# schematic.net
KiCad netlist of a schematic drawn in EasyEDA
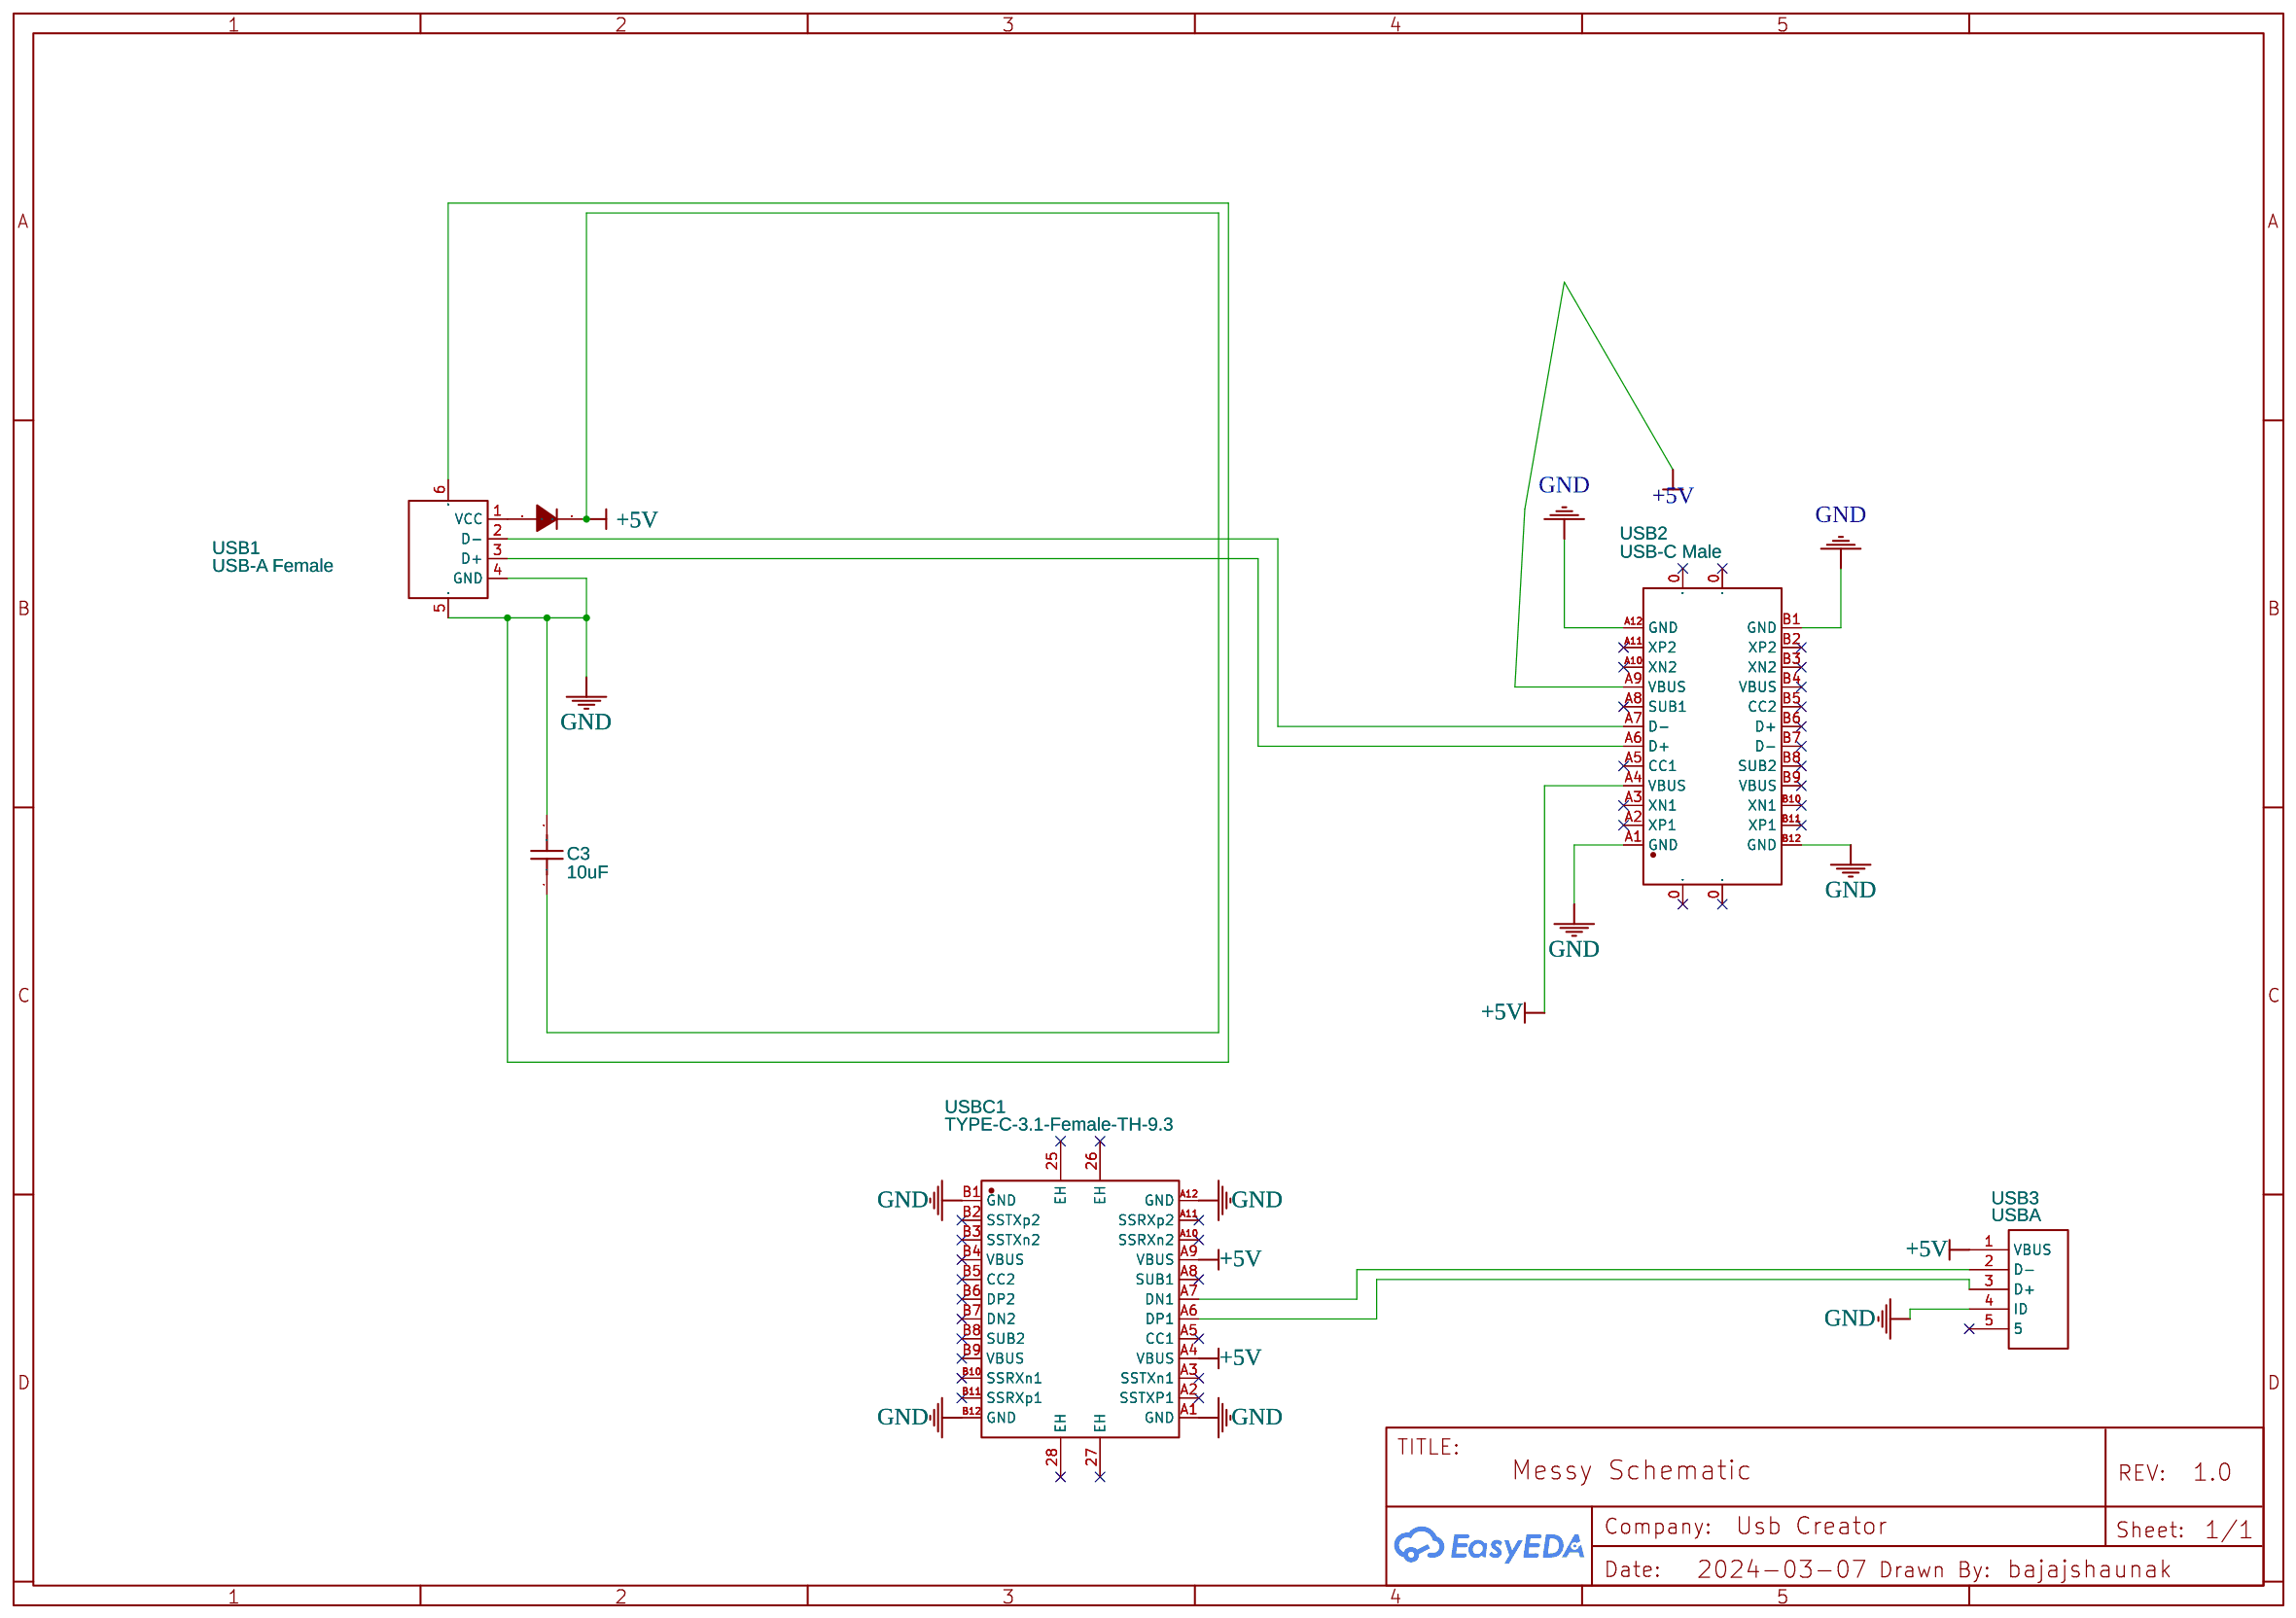
[diagram p0: schematic sheet]

(export (version "E")
  (design (tool "Eeschema 10.0.6"))
  (components
    (comp (ref "C3")
      (value "10uF")
      (fields
        (field (name "Manufacturer Part") "CL10A106KP8NNNC")
        (field (name "Manufacturer") "SAMSUNG(三星)")
      )
      (libsource (lib "") (part "CL10A106KP8NNNC"))
    )
    (comp (ref "D2")
      (value "NSR0320MW2T1G")
      (fields (field (name "Manufacturer") "onsemi(安森美)"))
      (libsource (lib "") (part "NSR0320MW2T1G"))
    )
    (comp (ref "USB1")
      (value "USB-A Female")
      (fields (field (name "Manufacturer Part") "USB-AF-DIP-154-HW-S") (field (name "Manufacturer") "皇捷"))
      (libsource (lib "") (part "USB-AF-DIP-154-HW-S"))
    )
    (comp (ref "USB2")
      (value "USB-C Male")
      (fields (field (name "Manufacturer Part") "USB-307HI") (field (name "Manufacturer") "HOOYA(皓宇电子)"))
      (libsource (lib "") (part "USB-307HI"))
    )
    (comp (ref "USB3")
      (value "USBA")
      (fields (field (name "Manufacturer Part") "U-USBAR04P-M001") (field (name "Manufacturer") "Ckmtw(灿科盟)"))
      (libsource (lib "") (part "U-USBAR04P-M002"))
    )
    (comp (ref "USBC1")
      (value "TYPE-C-3.1-Female-TH-9.3")
      (fields (field (name "Manufacturer Part") "918-418K2022Y40004") (field (name "Manufacturer") "精拓金"))
      (libsource (lib "") (part "TYPE-C-3.1-Female-TH-9.3"))
    )
  )
  (nets
    (net (code "1") (name "+5V") (class "Default")
      (node (ref "C3") (pin "1") (pinfunction "1_1") (pintype "unspecified"))
      (node (ref "D2") (pin "1") (pinfunction "C_1") (pintype "unspecified"))
      (node (ref "USB2") (pin "A4") (pinfunction "VBUS_A4") (pintype "unspecified"))
      (node (ref "USB2") (pin "A9") (pinfunction "VBUS_A9") (pintype "unspecified"))
      (node (ref "USB3") (pin "1") (pinfunction "VBUS_1") (pintype "unspecified"))
      (node (ref "USBC1") (pin "A4") (pinfunction "VBUS_A4") (pintype "unspecified"))
      (node (ref "USBC1") (pin "A9") (pinfunction "VBUS_A9") (pintype "unspecified"))
    )
    (net (code "2") (name "GND") (class "Default")
      (node (ref "C3") (pin "2") (pinfunction "2_2") (pintype "unspecified"))
      (node (ref "USB1") (pin "4") (pinfunction "GND_4") (pintype "input"))
      (node (ref "USB1") (pin "5") (pinfunction "SH1_5") (pintype "unspecified"))
      (node (ref "USB1") (pin "6") (pinfunction "SH2_6") (pintype "unspecified"))
      (node (ref "USB2") (pin "A1") (pinfunction "GND_A1") (pintype "unspecified"))
      (node (ref "USB2") (pin "A12") (pinfunction "GND_A12") (pintype "unspecified"))
      (node (ref "USB2") (pin "B1") (pinfunction "GND_B1") (pintype "unspecified"))
      (node (ref "USB2") (pin "B12") (pinfunction "GND_B12") (pintype "unspecified"))
      (node (ref "USB3") (pin "4") (pinfunction "ID_4") (pintype "unspecified"))
      (node (ref "USBC1") (pin "A1") (pinfunction "GND_A1") (pintype "unspecified"))
      (node (ref "USBC1") (pin "A12") (pinfunction "GND_A12") (pintype "unspecified"))
      (node (ref "USBC1") (pin "B1") (pinfunction "GND_B1") (pintype "unspecified"))
      (node (ref "USBC1") (pin "B12") (pinfunction "GND_B12") (pintype "unspecified"))
    )
    (net (code "3") (name "Net-(D2-A)") (class "Default")
      (node (ref "D2") (pin "2") (pinfunction "A_2") (pintype "unspecified"))
      (node (ref "USB1") (pin "1") (pinfunction "VCC_1") (pintype "input"))
    )
    (net (code "4") (name "Net-(USB1-D+)") (class "Default")
      (node (ref "USB1") (pin "3") (pinfunction "D+_3") (pintype "input"))
      (node (ref "USB2") (pin "A6") (pinfunction "D+_A6") (pintype "unspecified"))
    )
    (net (code "5") (name "Net-(USB1-D-)") (class "Default")
      (node (ref "USB1") (pin "2") (pinfunction "D-_2") (pintype "input"))
      (node (ref "USB2") (pin "A7") (pinfunction "D-_A7") (pintype "unspecified"))
    )
    (net (code "6") (name "Net-(USB3-D+)") (class "Default")
      (node (ref "USB3") (pin "3") (pinfunction "D+_3") (pintype "unspecified"))
      (node (ref "USBC1") (pin "A6") (pinfunction "DP1_A6") (pintype "unspecified"))
    )
    (net (code "7") (name "Net-(USB3-D-)") (class "Default")
      (node (ref "USB3") (pin "2") (pinfunction "D-_2") (pintype "unspecified"))
      (node (ref "USBC1") (pin "A7") (pinfunction "DN1_A7") (pintype "unspecified"))
    )
    (net (code "8") (name "unconnected-(USB2-CC1-PadA5)") (class "Default")
      (node (ref "USB2") (pin "A5") (pinfunction "CC1_A5") (pintype "unspecified+no_connect"))
    )
    (net (code "9") (name "unconnected-(USB2-CC2-PadB5)") (class "Default")
      (node (ref "USB2") (pin "B5") (pinfunction "CC2_B5") (pintype "unspecified+no_connect"))
    )
    (net (code "10") (name "unconnected-(USB2-D+-PadB6)") (class "Default")
      (node (ref "USB2") (pin "B6") (pinfunction "D+_B6") (pintype "unspecified+no_connect"))
    )
    (net (code "11") (name "unconnected-(USB2-D--PadB7)") (class "Default")
      (node (ref "USB2") (pin "B7") (pinfunction "D-_B7") (pintype "unspecified+no_connect"))
    )
    (net (code "12") (name "unconnected-(USB2-Pad0)") (class "Default")
      (node (ref "USB2") (pin "0") (pinfunction "0_0") (pintype "unspecified+no_connect"))
    )
    (net (code "13") (name "unconnected-(USB2-Pad0)_1") (class "Default")
      (node (ref "USB2") (pin "0") (pinfunction "0_0") (pintype "unspecified+no_connect"))
    )
    (net (code "14") (name "unconnected-(USB2-Pad0)_2") (class "Default")
      (node (ref "USB2") (pin "0") (pinfunction "0_0") (pintype "unspecified+no_connect"))
    )
    (net (code "15") (name "unconnected-(USB2-Pad0)_3") (class "Default")
      (node (ref "USB2") (pin "0") (pinfunction "0_0") (pintype "unspecified+no_connect"))
    )
    (net (code "16") (name "unconnected-(USB2-SUB1-PadA8)") (class "Default")
      (node (ref "USB2") (pin "A8") (pinfunction "SUB1_A8") (pintype "unspecified+no_connect"))
    )
    (net (code "17") (name "unconnected-(USB2-SUB2-PadB8)") (class "Default")
      (node (ref "USB2") (pin "B8") (pinfunction "SUB2_B8") (pintype "unspecified+no_connect"))
    )
    (net (code "18") (name "unconnected-(USB2-VBUS-PadB4)") (class "Default")
      (node (ref "USB2") (pin "B4") (pinfunction "VBUS_B4") (pintype "unspecified+no_connect"))
    )
    (net (code "19") (name "unconnected-(USB2-VBUS-PadB9)") (class "Default")
      (node (ref "USB2") (pin "B9") (pinfunction "VBUS_B9") (pintype "unspecified+no_connect"))
    )
    (net (code "20") (name "unconnected-(USB2-XN1-PadA3)") (class "Default")
      (node (ref "USB2") (pin "A3") (pinfunction "XN1_A3") (pintype "unspecified+no_connect"))
    )
    (net (code "21") (name "unconnected-(USB2-XN1-PadB10)") (class "Default")
      (node (ref "USB2") (pin "B10") (pinfunction "XN1_B10") (pintype "unspecified+no_connect"))
    )
    (net (code "22") (name "unconnected-(USB2-XN2-PadA10)") (class "Default")
      (node (ref "USB2") (pin "A10") (pinfunction "XN2_A10") (pintype "unspecified+no_connect"))
    )
    (net (code "23") (name "unconnected-(USB2-XN2-PadB3)") (class "Default")
      (node (ref "USB2") (pin "B3") (pinfunction "XN2_B3") (pintype "unspecified+no_connect"))
    )
    (net (code "24") (name "unconnected-(USB2-XP1-PadA2)") (class "Default")
      (node (ref "USB2") (pin "A2") (pinfunction "XP1_A2") (pintype "unspecified+no_connect"))
    )
    (net (code "25") (name "unconnected-(USB2-XP1-PadB11)") (class "Default")
      (node (ref "USB2") (pin "B11") (pinfunction "XP1_B11") (pintype "unspecified+no_connect"))
    )
    (net (code "26") (name "unconnected-(USB2-XP2-PadA11)") (class "Default")
      (node (ref "USB2") (pin "A11") (pinfunction "XP2_A11") (pintype "unspecified+no_connect"))
    )
    (net (code "27") (name "unconnected-(USB2-XP2-PadB2)") (class "Default")
      (node (ref "USB2") (pin "B2") (pinfunction "XP2_B2") (pintype "unspecified+no_connect"))
    )
    (net (code "28") (name "unconnected-(USB3-Pad5)") (class "Default")
      (node (ref "USB3") (pin "5") (pinfunction "5_5") (pintype "unspecified+no_connect"))
    )
    (net (code "29") (name "unconnected-(USBC1-CC1-PadA5)") (class "Default")
      (node (ref "USBC1") (pin "A5") (pinfunction "CC1_A5") (pintype "unspecified+no_connect"))
    )
    (net (code "30") (name "unconnected-(USBC1-CC2-PadB5)") (class "Default")
      (node (ref "USBC1") (pin "B5") (pinfunction "CC2_B5") (pintype "unspecified+no_connect"))
    )
    (net (code "31") (name "unconnected-(USBC1-DN2-PadB7)") (class "Default")
      (node (ref "USBC1") (pin "B7") (pinfunction "DN2_B7") (pintype "unspecified+no_connect"))
    )
    (net (code "32") (name "unconnected-(USBC1-DP2-PadB6)") (class "Default")
      (node (ref "USBC1") (pin "B6") (pinfunction "DP2_B6") (pintype "unspecified+no_connect"))
    )
    (net (code "33") (name "unconnected-(USBC1-EH-Pad25)") (class "Default")
      (node (ref "USBC1") (pin "25") (pinfunction "EH_25") (pintype "unspecified+no_connect"))
    )
    (net (code "34") (name "unconnected-(USBC1-EH-Pad26)") (class "Default")
      (node (ref "USBC1") (pin "26") (pinfunction "EH_26") (pintype "unspecified+no_connect"))
    )
    (net (code "35") (name "unconnected-(USBC1-EH-Pad27)") (class "Default")
      (node (ref "USBC1") (pin "27") (pinfunction "EH_27") (pintype "unspecified+no_connect"))
    )
    (net (code "36") (name "unconnected-(USBC1-EH-Pad28)") (class "Default")
      (node (ref "USBC1") (pin "28") (pinfunction "EH_28") (pintype "unspecified+no_connect"))
    )
    (net (code "37") (name "unconnected-(USBC1-SSRXn1-PadB10)") (class "Default")
      (node (ref "USBC1") (pin "B10") (pinfunction "SSRXn1_B10") (pintype "unspecified+no_connect"))
    )
    (net (code "38") (name "unconnected-(USBC1-SSRXn2-PadA10)") (class "Default")
      (node (ref "USBC1") (pin "A10") (pinfunction "SSRXn2_A10") (pintype "unspecified+no_connect"))
    )
    (net (code "39") (name "unconnected-(USBC1-SSRXp1-PadB11)") (class "Default")
      (node (ref "USBC1") (pin "B11") (pinfunction "SSRXp1_B11") (pintype "unspecified+no_connect"))
    )
    (net (code "40") (name "unconnected-(USBC1-SSRXp2-PadA11)") (class "Default")
      (node (ref "USBC1") (pin "A11") (pinfunction "SSRXp2_A11") (pintype "unspecified+no_connect"))
    )
    (net (code "41") (name "unconnected-(USBC1-SSTXP1-PadA2)") (class "Default")
      (node (ref "USBC1") (pin "A2") (pinfunction "SSTXP1_A2") (pintype "unspecified+no_connect"))
    )
    (net (code "42") (name "unconnected-(USBC1-SSTXn1-PadA3)") (class "Default")
      (node (ref "USBC1") (pin "A3") (pinfunction "SSTXn1_A3") (pintype "unspecified+no_connect"))
    )
    (net (code "43") (name "unconnected-(USBC1-SSTXn2-PadB3)") (class "Default")
      (node (ref "USBC1") (pin "B3") (pinfunction "SSTXn2_B3") (pintype "unspecified+no_connect"))
    )
    (net (code "44") (name "unconnected-(USBC1-SSTXp2-PadB2)") (class "Default")
      (node (ref "USBC1") (pin "B2") (pinfunction "SSTXp2_B2") (pintype "unspecified+no_connect"))
    )
    (net (code "45") (name "unconnected-(USBC1-SUB1-PadA8)") (class "Default")
      (node (ref "USBC1") (pin "A8") (pinfunction "SUB1_A8") (pintype "unspecified+no_connect"))
    )
    (net (code "46") (name "unconnected-(USBC1-SUB2-PadB8)") (class "Default")
      (node (ref "USBC1") (pin "B8") (pinfunction "SUB2_B8") (pintype "unspecified+no_connect"))
    )
    (net (code "47") (name "unconnected-(USBC1-VBUS-PadB4)") (class "Default")
      (node (ref "USBC1") (pin "B4") (pinfunction "VBUS_B4") (pintype "unspecified+no_connect"))
    )
    (net (code "48") (name "unconnected-(USBC1-VBUS-PadB9)") (class "Default")
      (node (ref "USBC1") (pin "B9") (pinfunction "VBUS_B9") (pintype "unspecified+no_connect"))
    )
  )
)
